# BSS123_divider_switch_simple.net
KiCad netlist of a schematic drawn in EAGLE
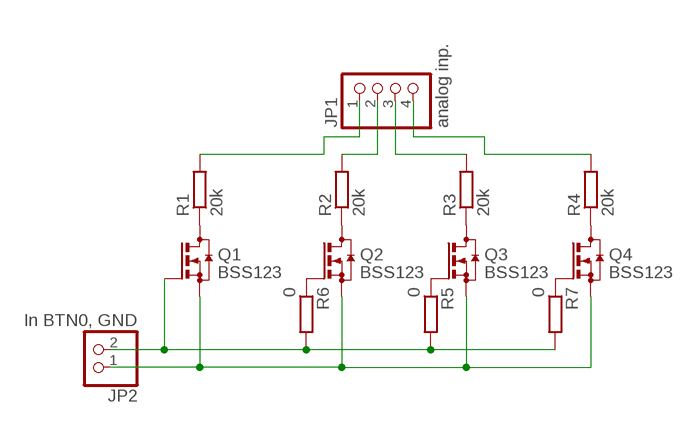
[diagram p0: schematic, sheet 1]

(export (version "E")
  (design (tool "Eeschema 10.0.6"))
  (components
    (comp (ref "JP1")
      (value "analog inp.")
      (footprint "eagle-import:1X04")
      (libsource (lib "eagle-import") (part "PINHD-1X4"))
    )
    (comp (ref "JP2")
      (value "In BTN0, GND")
      (footprint "eagle-import:1X02")
      (libsource (lib "eagle-import") (part "PINHD-1X2"))
    )
    (comp (ref "Q1")
      (value "BSS123")
      (footprint "eagle-import:SOT23")
      (libsource (lib "eagle-import") (part "BSS123"))
    )
    (comp (ref "Q2")
      (value "BSS123")
      (footprint "eagle-import:SOT23")
      (libsource (lib "eagle-import") (part "BSS123"))
    )
    (comp (ref "Q3")
      (value "BSS123")
      (footprint "eagle-import:SOT23")
      (libsource (lib "eagle-import") (part "BSS123"))
    )
    (comp (ref "Q4")
      (value "BSS123")
      (footprint "eagle-import:SOT23")
      (libsource (lib "eagle-import") (part "BSS123"))
    )
    (comp (ref "R1")
      (value "20k")
      (footprint "eagle-import:R1206")
      (libsource (lib "eagle-import") (part "R-EU_R1206"))
    )
    (comp (ref "R2")
      (value "20k")
      (footprint "eagle-import:R1206")
      (libsource (lib "eagle-import") (part "R-EU_R1206"))
    )
    (comp (ref "R3")
      (value "20k")
      (footprint "eagle-import:R1206")
      (libsource (lib "eagle-import") (part "R-EU_R1206"))
    )
    (comp (ref "R4")
      (value "20k")
      (footprint "eagle-import:R1206")
      (libsource (lib "eagle-import") (part "R-EU_R1206"))
    )
    (comp (ref "R5")
      (value "0")
      (footprint "eagle-import:R1206")
      (libsource (lib "eagle-import") (part "R-EU_R1206"))
    )
    (comp (ref "R6")
      (value "0")
      (footprint "eagle-import:R1206")
      (libsource (lib "eagle-import") (part "R-EU_R1206"))
    )
    (comp (ref "R7")
      (value "0")
      (footprint "eagle-import:R1206")
      (libsource (lib "eagle-import") (part "R-EU_R1206"))
    )
  )
  (nets
    (net (code "1") (name "Net-(JP1-Pad1)") (class "Default")
      (node (ref "JP1") (pin "1") (pinfunction "1_1") (pintype "passive"))
      (node (ref "R1") (pin "2") (pinfunction "2_2") (pintype "passive"))
    )
    (net (code "2") (name "Net-(JP1-Pad2)") (class "Default")
      (node (ref "JP1") (pin "2") (pinfunction "2_2") (pintype "passive"))
      (node (ref "R2") (pin "2") (pinfunction "2_2") (pintype "passive"))
    )
    (net (code "3") (name "Net-(JP1-Pad3)") (class "Default")
      (node (ref "JP1") (pin "3") (pinfunction "3_3") (pintype "passive"))
      (node (ref "R3") (pin "2") (pinfunction "2_2") (pintype "passive"))
    )
    (net (code "4") (name "Net-(JP1-Pad4)") (class "Default")
      (node (ref "JP1") (pin "4") (pinfunction "4_4") (pintype "passive"))
      (node (ref "R4") (pin "2") (pinfunction "2_2") (pintype "passive"))
    )
    (net (code "5") (name "Net-(Q1-D)") (class "Default")
      (node (ref "Q1") (pin "3") (pinfunction "D_3") (pintype "passive"))
      (node (ref "R1") (pin "1") (pinfunction "1_1") (pintype "passive"))
    )
    (net (code "6") (name "Net-(Q1-G)") (class "Default")
      (node (ref "JP2") (pin "2") (pinfunction "2_2") (pintype "passive"))
      (node (ref "Q1") (pin "1") (pinfunction "G_1") (pintype "passive"))
      (node (ref "R5") (pin "2") (pinfunction "2_2") (pintype "passive"))
      (node (ref "R6") (pin "2") (pinfunction "2_2") (pintype "passive"))
      (node (ref "R7") (pin "2") (pinfunction "2_2") (pintype "passive"))
    )
    (net (code "7") (name "Net-(Q1-S)") (class "Default")
      (node (ref "JP2") (pin "1") (pinfunction "1_1") (pintype "passive"))
      (node (ref "Q1") (pin "2") (pinfunction "S_2") (pintype "passive"))
      (node (ref "Q2") (pin "2") (pinfunction "S_2") (pintype "passive"))
      (node (ref "Q3") (pin "2") (pinfunction "S_2") (pintype "passive"))
      (node (ref "Q4") (pin "2") (pinfunction "S_2") (pintype "passive"))
    )
    (net (code "8") (name "Net-(Q2-D)") (class "Default")
      (node (ref "Q2") (pin "3") (pinfunction "D_3") (pintype "passive"))
      (node (ref "R2") (pin "1") (pinfunction "1_1") (pintype "passive"))
    )
    (net (code "9") (name "Net-(Q2-G)") (class "Default")
      (node (ref "Q2") (pin "1") (pinfunction "G_1") (pintype "passive"))
      (node (ref "R6") (pin "1") (pinfunction "1_1") (pintype "passive"))
    )
    (net (code "10") (name "Net-(Q3-D)") (class "Default")
      (node (ref "Q3") (pin "3") (pinfunction "D_3") (pintype "passive"))
      (node (ref "R3") (pin "1") (pinfunction "1_1") (pintype "passive"))
    )
    (net (code "11") (name "Net-(Q3-G)") (class "Default")
      (node (ref "Q3") (pin "1") (pinfunction "G_1") (pintype "passive"))
      (node (ref "R5") (pin "1") (pinfunction "1_1") (pintype "passive"))
    )
    (net (code "12") (name "Net-(Q4-D)") (class "Default")
      (node (ref "Q4") (pin "3") (pinfunction "D_3") (pintype "passive"))
      (node (ref "R4") (pin "1") (pinfunction "1_1") (pintype "passive"))
    )
    (net (code "13") (name "Net-(Q4-G)") (class "Default")
      (node (ref "Q4") (pin "1") (pinfunction "G_1") (pintype "passive"))
      (node (ref "R7") (pin "1") (pinfunction "1_1") (pintype "passive"))
    )
  )
)
